# Adafruit_DS3231_RTC_Breakout.net
KiCad netlist of a schematic drawn in EAGLE
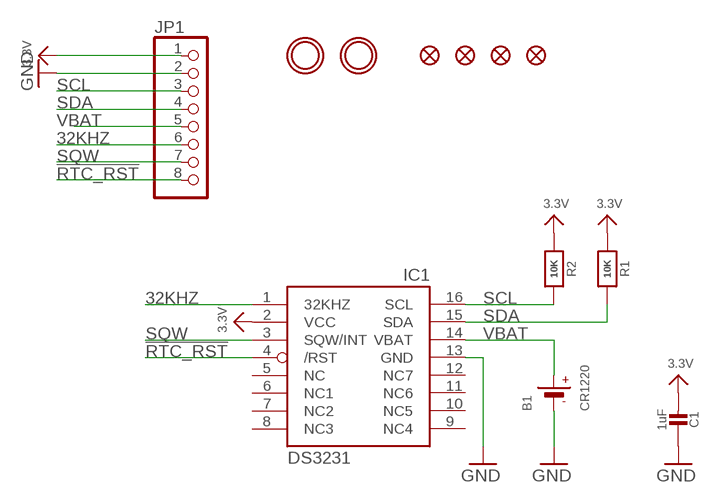
[diagram p0: schematic, sheet 1]

(export (version "E")
  (design (tool "Eeschema 10.0.6"))
  (components
    (comp (ref "B1")
      (value "CR1220")
      (footprint "eagle-import:CR1220")
      (libsource (lib "eagle-import") (part "BATTERYCR1220_SMT"))
    )
    (comp (ref "C1")
      (value "1uF")
      (footprint "eagle-import:0805-NO")
      (libsource (lib "eagle-import") (part "CAP_CERAMIC0805-NOOUTLINE"))
    )
    (comp (ref "FID1")
      (value "FIDUCIAL\"\"")
      (footprint "eagle-import:FIDUCIAL_1MM")
      (libsource (lib "eagle-import") (part "FIDUCIAL{dblquote}{dblquote}"))
    )
    (comp (ref "FID2")
      (value "FIDUCIAL\"\"")
      (footprint "eagle-import:FIDUCIAL_1MM")
      (libsource (lib "eagle-import") (part "FIDUCIAL{dblquote}{dblquote}"))
    )
    (comp (ref "FID3")
      (value "FIDUCIAL\"\"")
      (footprint "eagle-import:FIDUCIAL_1MM")
      (libsource (lib "eagle-import") (part "FIDUCIAL{dblquote}{dblquote}"))
    )
    (comp (ref "FID4")
      (value "FIDUCIAL\"\"")
      (footprint "eagle-import:FIDUCIAL_1MM")
      (libsource (lib "eagle-import") (part "FIDUCIAL{dblquote}{dblquote}"))
    )
    (comp (ref "IC1")
      (value "DS3231/SO")
      (footprint "eagle-import:SO16W")
      (libsource (lib "eagle-import") (part "DS3231/SO"))
    )
    (comp (ref "JP1")
      (value "HEADER-1X870MIL")
      (footprint "eagle-import:1X08_ROUND_70")
      (libsource (lib "eagle-import") (part "HEADER-1X870MIL"))
    )
    (comp (ref "R1")
      (value "10K")
      (footprint "eagle-import:0805-NO")
      (libsource (lib "eagle-import") (part "RESISTOR0805_NOOUTLINE"))
    )
    (comp (ref "R2")
      (value "10K")
      (footprint "eagle-import:0805-NO")
      (libsource (lib "eagle-import") (part "RESISTOR0805_NOOUTLINE"))
    )
    (comp (ref "U$6")
      (value "MOUNTINGHOLE2.5")
      (footprint "eagle-import:MOUNTINGHOLE_2.5_PLATED")
      (libsource (lib "eagle-import") (part "MOUNTINGHOLE2.5"))
    )
    (comp (ref "U$7")
      (value "MOUNTINGHOLE2.5")
      (footprint "eagle-import:MOUNTINGHOLE_2.5_PLATED")
      (libsource (lib "eagle-import") (part "MOUNTINGHOLE2.5"))
    )
  )
  (nets
    (net (code "1") (name "/32KHZ") (class "Default")
      (node (ref "IC1") (pin "1") (pinfunction "32KHZ_1") (pintype "output"))
      (node (ref "JP1") (pin "6") (pinfunction "6_6") (pintype "passive"))
    )
    (net (code "2") (name "/SCL") (class "Default")
      (node (ref "IC1") (pin "16") (pinfunction "SCL_16") (pintype "bidirectional"))
      (node (ref "JP1") (pin "3") (pinfunction "3_3") (pintype "passive"))
      (node (ref "R2") (pin "2") (pinfunction "2_2") (pintype "passive"))
    )
    (net (code "3") (name "/SDA") (class "Default")
      (node (ref "IC1") (pin "15") (pinfunction "SDA_15") (pintype "bidirectional"))
      (node (ref "JP1") (pin "4") (pinfunction "4_4") (pintype "passive"))
      (node (ref "R1") (pin "2") (pinfunction "2_2") (pintype "passive"))
    )
    (net (code "4") (name "/SQW") (class "Default")
      (node (ref "IC1") (pin "3") (pinfunction "SQW/INT_3") (pintype "output"))
      (node (ref "JP1") (pin "7") (pinfunction "7_7") (pintype "passive"))
    )
    (net (code "5") (name "/VBAT") (class "Default")
      (node (ref "B1") (pin "+$1") (pinfunction "+_+$1") (pintype "passive"))
      (node (ref "IC1") (pin "14") (pinfunction "VBAT_14") (pintype "power_in"))
      (node (ref "JP1") (pin "5") (pinfunction "5_5") (pintype "passive"))
    )
    (net (code "6") (name "/~{RTC_RST}") (class "Default")
      (node (ref "IC1") (pin "4") (pinfunction "/RST_4") (pintype "passive"))
      (node (ref "JP1") (pin "8") (pinfunction "8_8") (pintype "passive"))
    )
    (net (code "7") (name "3.3V") (class "Default")
      (node (ref "C1") (pin "2") (pinfunction "2_2") (pintype "passive"))
      (node (ref "IC1") (pin "2") (pinfunction "VCC_2") (pintype "power_in"))
      (node (ref "JP1") (pin "1") (pinfunction "1_1") (pintype "passive"))
      (node (ref "R1") (pin "1") (pinfunction "1_1") (pintype "passive"))
      (node (ref "R2") (pin "1") (pinfunction "1_1") (pintype "passive"))
    )
    (net (code "8") (name "GND") (class "Default")
      (node (ref "B1") (pin "-") (pinfunction "-_-") (pintype "passive"))
      (node (ref "C1") (pin "1") (pinfunction "1_1") (pintype "passive"))
      (node (ref "IC1") (pin "13") (pinfunction "GND_13") (pintype "power_in"))
      (node (ref "JP1") (pin "2") (pinfunction "2_2") (pintype "passive"))
    )
    (net (code "9") (name "unconnected-(IC1-NC-Pad5)") (class "Default")
      (node (ref "IC1") (pin "5") (pinfunction "NC_5") (pintype "no_connect"))
    )
    (net (code "10") (name "unconnected-(IC1-NC1-Pad6)") (class "Default")
      (node (ref "IC1") (pin "6") (pinfunction "NC1_6") (pintype "no_connect"))
    )
    (net (code "11") (name "unconnected-(IC1-NC2-Pad7)") (class "Default")
      (node (ref "IC1") (pin "7") (pinfunction "NC2_7") (pintype "no_connect"))
    )
    (net (code "12") (name "unconnected-(IC1-NC3-Pad8)") (class "Default")
      (node (ref "IC1") (pin "8") (pinfunction "NC3_8") (pintype "no_connect"))
    )
    (net (code "13") (name "unconnected-(IC1-NC4-Pad9)") (class "Default")
      (node (ref "IC1") (pin "9") (pinfunction "NC4_9") (pintype "no_connect"))
    )
    (net (code "14") (name "unconnected-(IC1-NC5-Pad10)") (class "Default")
      (node (ref "IC1") (pin "10") (pinfunction "NC5_10") (pintype "no_connect"))
    )
    (net (code "15") (name "unconnected-(IC1-NC6-Pad11)") (class "Default")
      (node (ref "IC1") (pin "11") (pinfunction "NC6_11") (pintype "no_connect"))
    )
    (net (code "16") (name "unconnected-(IC1-NC7-Pad12)") (class "Default")
      (node (ref "IC1") (pin "12") (pinfunction "NC7_12") (pintype "no_connect"))
    )
  )
)
